# V1_0.net
KiCad netlist of a schematic drawn in Altium Designer
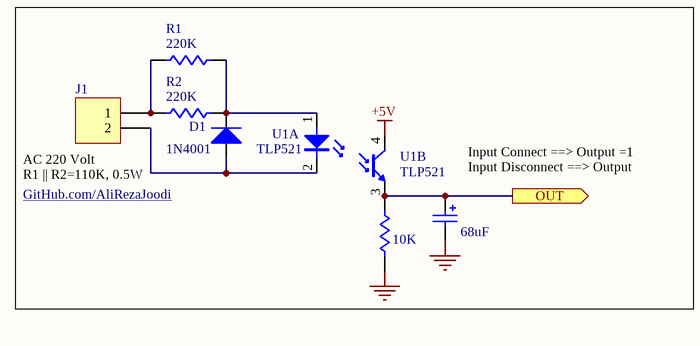
[diagram p0: V1.0.SchDoc]

(export (version "E")
  (design (tool "Eeschema 10.0.6"))
  (components
    (comp (ref "C1")
      (value "68uF")
      (footprint "Cap_D")
      (description "Polarized Capacitor (Radial)")
      (fields
        (field (name "MANUFACTURER") "Generic Components")
        (field (name "Comment") "CAP")
        (field (name "PUBLISHER") "Altium Limited")
      )
      (libsource (lib "Miscellaneous Devices") (part "Cap Pol1"))
    )
    (comp (ref "D1")
      (value "1N4001")
      (footprint "MELF-D3516-1406")
      (description "Default Diode")
      (fields (field (name "MANUFACTURER") "Generic Components") (field (name "PUBLISHER") "Altium Limited"))
      (libsource (lib "Miscellaneous Devices") (part "Diode"))
    )
    (comp (ref "J1")
      (value "J9")
      (footprint "Fonics_2PIN_1")
      (description "Header, 2-Pin")
      (fields (field (name "PUBLISHER") "Altium Limited"))
      (libsource (lib "Miscellaneous Connectors") (part "Header 2"))
    )
    (comp (ref "R1")
      (value "220K")
      (footprint "0805")
      (description "Resistor")
      (fields
        (field (name "MANUFACTURER") "Generic Components")
        (field (name "Comment") "RES")
        (field (name "PUBLISHER") "Altium Limited")
      )
      (libsource (lib "Miscellaneous Devices") (part "Res1"))
    )
    (comp (ref "R2")
      (value "220K")
      (footprint "0805")
      (description "Resistor")
      (fields
        (field (name "MANUFACTURER") "Generic Components")
        (field (name "Comment") "RES")
        (field (name "PUBLISHER") "Altium Limited")
      )
      (libsource (lib "Miscellaneous Devices") (part "Res1"))
    )
    (comp (ref "R3")
      (value "10K")
      (footprint "0805")
      (description "Resistor")
      (fields
        (field (name "MANUFACTURER") "Generic Components")
        (field (name "Comment") "RES")
        (field (name "PUBLISHER") "Altium Limited")
      )
      (libsource (lib "Miscellaneous Devices") (part "Res1"))
    )
    (comp (ref "U1")
      (value "TLP521")
      (footprint "SMD_4PIN")
      (fields (field (name "PUBLISHER") "Altium Limited"))
      (libsource (lib "my Libraries") (part "Optoisolator"))
    )
  )
  (nets
    (net (code "1") (name "+5V") (class "Default")
      (node (ref "U1") (pin "4") (pinfunction "C_4") (pintype "passive"))
    )
    (net (code "2") (name "/OUT") (class "Default")
      (node (ref "C1") (pin "1") (pinfunction "1_1") (pintype "passive"))
      (node (ref "R3") (pin "1") (pinfunction "1_1") (pintype "passive"))
      (node (ref "U1") (pin "3") (pinfunction "E_3") (pintype "passive"))
    )
    (net (code "3") (name "GND") (class "Default")
      (node (ref "C1") (pin "2") (pinfunction "2_2") (pintype "passive"))
      (node (ref "R3") (pin "2") (pinfunction "2_2") (pintype "passive"))
    )
    (net (code "4") (name "Net-(D1-A)") (class "Default")
      (node (ref "D1") (pin "1") (pinfunction "A_1") (pintype "passive"))
      (node (ref "J1") (pin "2") (pinfunction "2_2") (pintype "passive"))
      (node (ref "U1") (pin "2") (pinfunction "K_2") (pintype "power_in"))
    )
    (net (code "5") (name "Net-(D1-K)") (class "Default")
      (node (ref "D1") (pin "2") (pinfunction "K_2") (pintype "passive"))
      (node (ref "R1") (pin "2") (pinfunction "2_2") (pintype "passive"))
      (node (ref "R2") (pin "2") (pinfunction "2_2") (pintype "passive"))
      (node (ref "U1") (pin "1") (pinfunction "A_1") (pintype "power_in"))
    )
    (net (code "6") (name "Net-(J1-Pad1)") (class "Default")
      (node (ref "J1") (pin "1") (pinfunction "1_1") (pintype "passive"))
      (node (ref "R1") (pin "1") (pinfunction "1_1") (pintype "passive"))
      (node (ref "R2") (pin "1") (pinfunction "1_1") (pintype "passive"))
    )
  )
)
